# tach_adapter.net
KiCad netlist of a schematic drawn in EAGLE
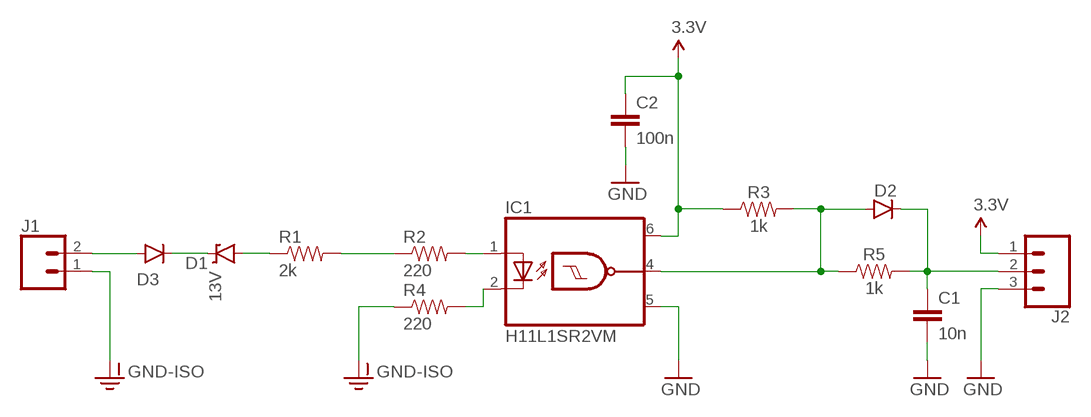
[diagram p0: schematic, sheet 1]

(export (version "E")
  (design (tool "Eeschema 10.0.6"))
  (components
    (comp (ref "C1")
      (value "10n")
      (footprint "eagle-import:0603")
      (fields (field (name "VOLTAGE") "50V"))
      (libsource (lib "eagle-import") (part "CL10B103KB8NNNC"))
    )
    (comp (ref "C2")
      (value "100n")
      (footprint "eagle-import:0603")
      (fields (field (name "VOLTAGE") "50V"))
      (libsource (lib "eagle-import") (part "CL10B104MB8NNNC"))
    )
    (comp (ref "D1")
      (value "13V")
      (footprint "eagle-import:SMB-DIODE")
      (libsource (lib "eagle-import") (part "DIODE-ZENERSMB"))
    )
    (comp (ref "D2")
      (value "DIODESMA")
      (footprint "eagle-import:SMA-DIODE")
      (libsource (lib "eagle-import") (part "DIODESMA"))
    )
    (comp (ref "D3")
      (value "DIODESMA")
      (footprint "eagle-import:SMA-DIODE")
      (libsource (lib "eagle-import") (part "DIODESMA"))
    )
    (comp (ref "IC1")
      (value "H11L1SR2VM")
      (footprint "eagle-import:6-SMD")
      (libsource (lib "eagle-import") (part "H11L1SR2VM"))
    )
    (comp (ref "J1")
      (value "CONN_02LARGE")
      (footprint "eagle-import:1X02_LARGE")
      (libsource (lib "eagle-import") (part "CONN_02LARGE"))
    )
    (comp (ref "J2")
      (value "CONN_031X03_LARGE")
      (footprint "eagle-import:1X03_LARGE")
      (libsource (lib "eagle-import") (part "CONN_031X03_LARGE"))
    )
    (comp (ref "R1")
      (value "2k")
      (footprint "eagle-import:1206")
      (libsource (lib "eagle-import") (part "RESISTOR1206"))
    )
    (comp (ref "R2")
      (value "220")
      (footprint "eagle-import:1206")
      (libsource (lib "eagle-import") (part "RESISTOR1206"))
    )
    (comp (ref "R3")
      (value "1k")
      (footprint "eagle-import:0603")
      (libsource (lib "eagle-import") (part "RC0603JR-071KL"))
    )
    (comp (ref "R4")
      (value "220")
      (footprint "eagle-import:1206")
      (libsource (lib "eagle-import") (part "RESISTOR1206"))
    )
    (comp (ref "R5")
      (value "1k")
      (footprint "eagle-import:0603")
      (libsource (lib "eagle-import") (part "RC0603JR-071KL"))
    )
  )
  (nets
    (net (code "1") (name "3.3V") (class "Default")
      (node (ref "C2") (pin "1") (pinfunction "1_1") (pintype "passive"))
      (node (ref "IC1") (pin "6") (pinfunction "VCC_6") (pintype "passive"))
      (node (ref "J2") (pin "1") (pinfunction "1_1") (pintype "passive"))
      (node (ref "R3") (pin "1") (pinfunction "1_1") (pintype "passive"))
    )
    (net (code "2") (name "GND") (class "Default")
      (node (ref "C1") (pin "2") (pinfunction "2_2") (pintype "passive"))
      (node (ref "C2") (pin "2") (pinfunction "2_2") (pintype "passive"))
      (node (ref "IC1") (pin "5") (pinfunction "GND_5") (pintype "passive"))
      (node (ref "J2") (pin "3") (pinfunction "3_3") (pintype "passive"))
    )
    (net (code "3") (name "GND-ISO") (class "Default")
      (node (ref "J1") (pin "1") (pinfunction "1_1") (pintype "passive"))
      (node (ref "R4") (pin "1") (pinfunction "1_1") (pintype "passive"))
    )
    (net (code "4") (name "Net-(C1-Pad1)") (class "Default")
      (node (ref "C1") (pin "1") (pinfunction "1_1") (pintype "passive"))
      (node (ref "D2") (pin "C") (pinfunction "C_C") (pintype "passive"))
      (node (ref "J2") (pin "2") (pinfunction "2_2") (pintype "passive"))
      (node (ref "R5") (pin "2") (pinfunction "2_2") (pintype "passive"))
    )
    (net (code "5") (name "Net-(D1-PadA)") (class "Default")
      (node (ref "D1") (pin "A") (pinfunction "A_A") (pintype "passive"))
      (node (ref "R1") (pin "1") (pinfunction "1_1") (pintype "passive"))
    )
    (net (code "6") (name "Net-(D1-PadC)") (class "Default")
      (node (ref "D1") (pin "C") (pinfunction "C_C") (pintype "passive"))
      (node (ref "D3") (pin "C") (pinfunction "C_C") (pintype "passive"))
    )
    (net (code "7") (name "Net-(D3-PadA)") (class "Default")
      (node (ref "D3") (pin "A") (pinfunction "A_A") (pintype "passive"))
      (node (ref "J1") (pin "2") (pinfunction "2_2") (pintype "passive"))
    )
    (net (code "8") (name "Net-(IC1-A)") (class "Default")
      (node (ref "IC1") (pin "1") (pinfunction "A_1") (pintype "passive"))
      (node (ref "R2") (pin "2") (pinfunction "2_2") (pintype "passive"))
    )
    (net (code "9") (name "Net-(IC1-C)") (class "Default")
      (node (ref "IC1") (pin "2") (pinfunction "C_2") (pintype "passive"))
      (node (ref "R4") (pin "2") (pinfunction "2_2") (pintype "passive"))
    )
    (net (code "10") (name "Net-(IC1-VOUT)") (class "Default")
      (node (ref "D2") (pin "A") (pinfunction "A_A") (pintype "passive"))
      (node (ref "IC1") (pin "4") (pinfunction "VOUT_4") (pintype "passive"))
      (node (ref "R3") (pin "2") (pinfunction "2_2") (pintype "passive"))
      (node (ref "R5") (pin "1") (pinfunction "1_1") (pintype "passive"))
    )
    (net (code "11") (name "Net-(R1-Pad2)") (class "Default")
      (node (ref "R1") (pin "2") (pinfunction "2_2") (pintype "passive"))
      (node (ref "R2") (pin "1") (pinfunction "1_1") (pintype "passive"))
    )
  )
)
